# Sch_PowerSupplyLM2596.net
KiCad netlist of a schematic drawn in Altium Designer
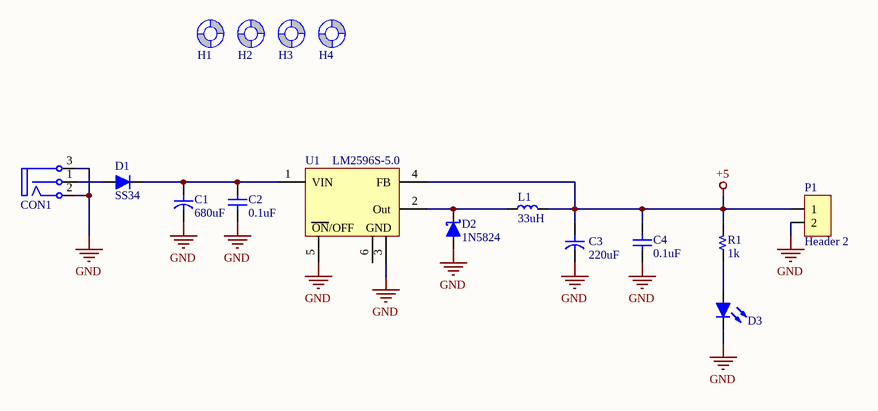
[diagram p0: Sch_PowerSupplyLM2596.SchDoc]

(export (version "E")
  (design (tool "Eeschema 10.0.6"))
  (components
    (comp (ref "C1")
      (value "680uF")
      (footprint "CYL/D.500/LS.200")
      (description "Capacitor pol")
      (libsource (lib "chipfc_altium_libs") (part "Capacitor"))
    )
    (comp (ref "C2")
      (value "0.1uF")
      (footprint "C 0805")
      (description "Capacitor non-pol")
      (libsource (lib "chipfc_altium_libs") (part "Capacitor NP"))
    )
    (comp (ref "C3")
      (value "220uF")
      (footprint "CYL/D.500/LS.200")
      (description "Capacitor pol")
      (libsource (lib "chipfc_altium_libs") (part "Capacitor"))
    )
    (comp (ref "C4")
      (value "0.1uF")
      (footprint "C 0805")
      (description "Capacitor non-pol")
      (libsource (lib "chipfc_altium_libs") (part "Capacitor NP"))
    )
    (comp (ref "CON1")
      (value "CON DC PWR")
      (footprint "CONN/DC/PWR/5.0MM")
      (description "DC input connector")
      (libsource (lib "chipfc_altium_libs") (part "CON DC PWR"))
    )
    (comp (ref "D1")
      (value "SS34")
      (footprint "DO-214AC (SMA)")
      (description "Default Diode")
      (libsource (lib "chipfc_altium_libs") (part "Diode"))
    )
    (comp (ref "D2")
      (value "1N5824")
      (footprint "DO-214AC (SMA)")
      (description "Schottky Diode")
      (libsource (lib "chipfc_altium_libs") (part "Diode Schottky"))
    )
    (comp (ref "D3")
      (value "Led")
      (footprint "Led 0805 RED")
      (description "Typical LED")
      (libsource (lib "chipfc_altium_libs") (part "Led"))
    )
    (comp (ref "H1")
      (value "Screw Hole")
      (footprint "SCREW/3.2/7.0/M")
      (libsource (lib "chipfc_altium_libs") (part "Screw Hole"))
    )
    (comp (ref "H2")
      (value "Screw Hole")
      (footprint "SCREW/3.2/7.0/M")
      (libsource (lib "chipfc_altium_libs") (part "Screw Hole"))
    )
    (comp (ref "H3")
      (value "Screw Hole")
      (footprint "SCREW/3.2/7.0/M")
      (libsource (lib "chipfc_altium_libs") (part "Screw Hole"))
    )
    (comp (ref "H4")
      (value "Screw Hole")
      (footprint "SCREW/3.2/7.0/M")
      (libsource (lib "chipfc_altium_libs") (part "Screw Hole"))
    )
    (comp (ref "L1")
      (value "33uH")
      (footprint "Inductor SMD 12x12x8")
      (description "Inductor")
      (libsource (lib "chipfc_altium_libs") (part "Inductor"))
    )
    (comp (ref "P1")
      (value "Header 2")
      (footprint "HDR/Header/2/VH")
      (description "Header, 2-Pin")
      (libsource (lib "chipfc_altium_libs") (part "Header 2"))
    )
    (comp (ref "R1")
      (value "1k")
      (footprint "R 0805")
      (description "Resistor")
      (libsource (lib "chipfc_altium_libs") (part "Resistor"))
    )
    (comp (ref "U1")
      (value "LM2596S-5.0")
      (footprint "TO-263-5")
      (description "Simple Switcher 3A Step-Down Voltage Regulator")
      (libsource (lib "chipfc_altium_libs") (part "LM2596S-5.0"))
    )
  )
  (nets
    (net (code "1") (name "+5") (class "Default")
      (node (ref "C3") (pin "1") (pinfunction "1_1") (pintype "passive"))
      (node (ref "C4") (pin "1") (pinfunction "1_1") (pintype "passive"))
      (node (ref "L1") (pin "2") (pinfunction "2_2") (pintype "passive"))
      (node (ref "P1") (pin "1") (pinfunction "1_1") (pintype "passive"))
      (node (ref "R1") (pin "2") (pinfunction "2_2") (pintype "passive"))
      (node (ref "U1") (pin "4") (pinfunction "FB_4") (pintype "passive"))
    )
    (net (code "2") (name "GND") (class "Default")
      (node (ref "C1") (pin "2") (pinfunction "2_2") (pintype "passive"))
      (node (ref "C2") (pin "2") (pinfunction "2_2") (pintype "passive"))
      (node (ref "C3") (pin "2") (pinfunction "2_2") (pintype "passive"))
      (node (ref "C4") (pin "2") (pinfunction "2_2") (pintype "passive"))
      (node (ref "CON1") (pin "2") (pinfunction "T_2") (pintype "passive"))
      (node (ref "CON1") (pin "3") (pinfunction "TN_3") (pintype "passive"))
      (node (ref "D2") (pin "1") (pinfunction "A_1") (pintype "passive"))
      (node (ref "D3") (pin "2") (pinfunction "K_2") (pintype "passive"))
      (node (ref "P1") (pin "2") (pinfunction "2_2") (pintype "passive"))
      (node (ref "U1") (pin "3") (pinfunction "GND_3") (pintype "passive"))
      (node (ref "U1") (pin "5") (pinfunction "~{ON}/OFF_5") (pintype "passive"))
    )
    (net (code "3") (name "Net-(CON1-S)") (class "Default")
      (node (ref "CON1") (pin "1") (pinfunction "S_1") (pintype "power_in"))
      (node (ref "D1") (pin "1") (pinfunction "A_1") (pintype "passive"))
    )
    (net (code "4") (name "Net-(D1-K)") (class "Default")
      (node (ref "C1") (pin "1") (pinfunction "1_1") (pintype "passive"))
      (node (ref "C2") (pin "1") (pinfunction "1_1") (pintype "passive"))
      (node (ref "D1") (pin "2") (pinfunction "K_2") (pintype "passive"))
      (node (ref "U1") (pin "1") (pinfunction "VIN_1") (pintype "passive"))
    )
    (net (code "5") (name "Net-(D2-K)") (class "Default")
      (node (ref "D2") (pin "2") (pinfunction "K_2") (pintype "passive"))
      (node (ref "L1") (pin "1") (pinfunction "1_1") (pintype "passive"))
      (node (ref "U1") (pin "2") (pinfunction "Out_2") (pintype "passive"))
    )
    (net (code "6") (name "Net-(D3-A)") (class "Default")
      (node (ref "D3") (pin "1") (pinfunction "A_1") (pintype "passive"))
      (node (ref "R1") (pin "1") (pinfunction "1_1") (pintype "passive"))
    )
    (net (code "7") (name "unconnected-(H1-Screw-Pad1)") (class "Default")
      (node (ref "H1") (pin "1") (pinfunction "Screw_1") (pintype "passive"))
    )
    (net (code "8") (name "unconnected-(H2-Screw-Pad1)") (class "Default")
      (node (ref "H2") (pin "1") (pinfunction "Screw_1") (pintype "passive"))
    )
    (net (code "9") (name "unconnected-(H3-Screw-Pad1)") (class "Default")
      (node (ref "H3") (pin "1") (pinfunction "Screw_1") (pintype "passive"))
    )
    (net (code "10") (name "unconnected-(H4-Screw-Pad1)") (class "Default")
      (node (ref "H4") (pin "1") (pinfunction "Screw_1") (pintype "passive"))
    )
    (net (code "11") (name "unconnected-(U1-PAD-Pad6)") (class "Default")
      (node (ref "U1") (pin "6") (pinfunction "PAD_6") (pintype "passive"))
    )
  )
)
